# XOR_1_1.net
KiCad netlist of a schematic drawn in EAGLE
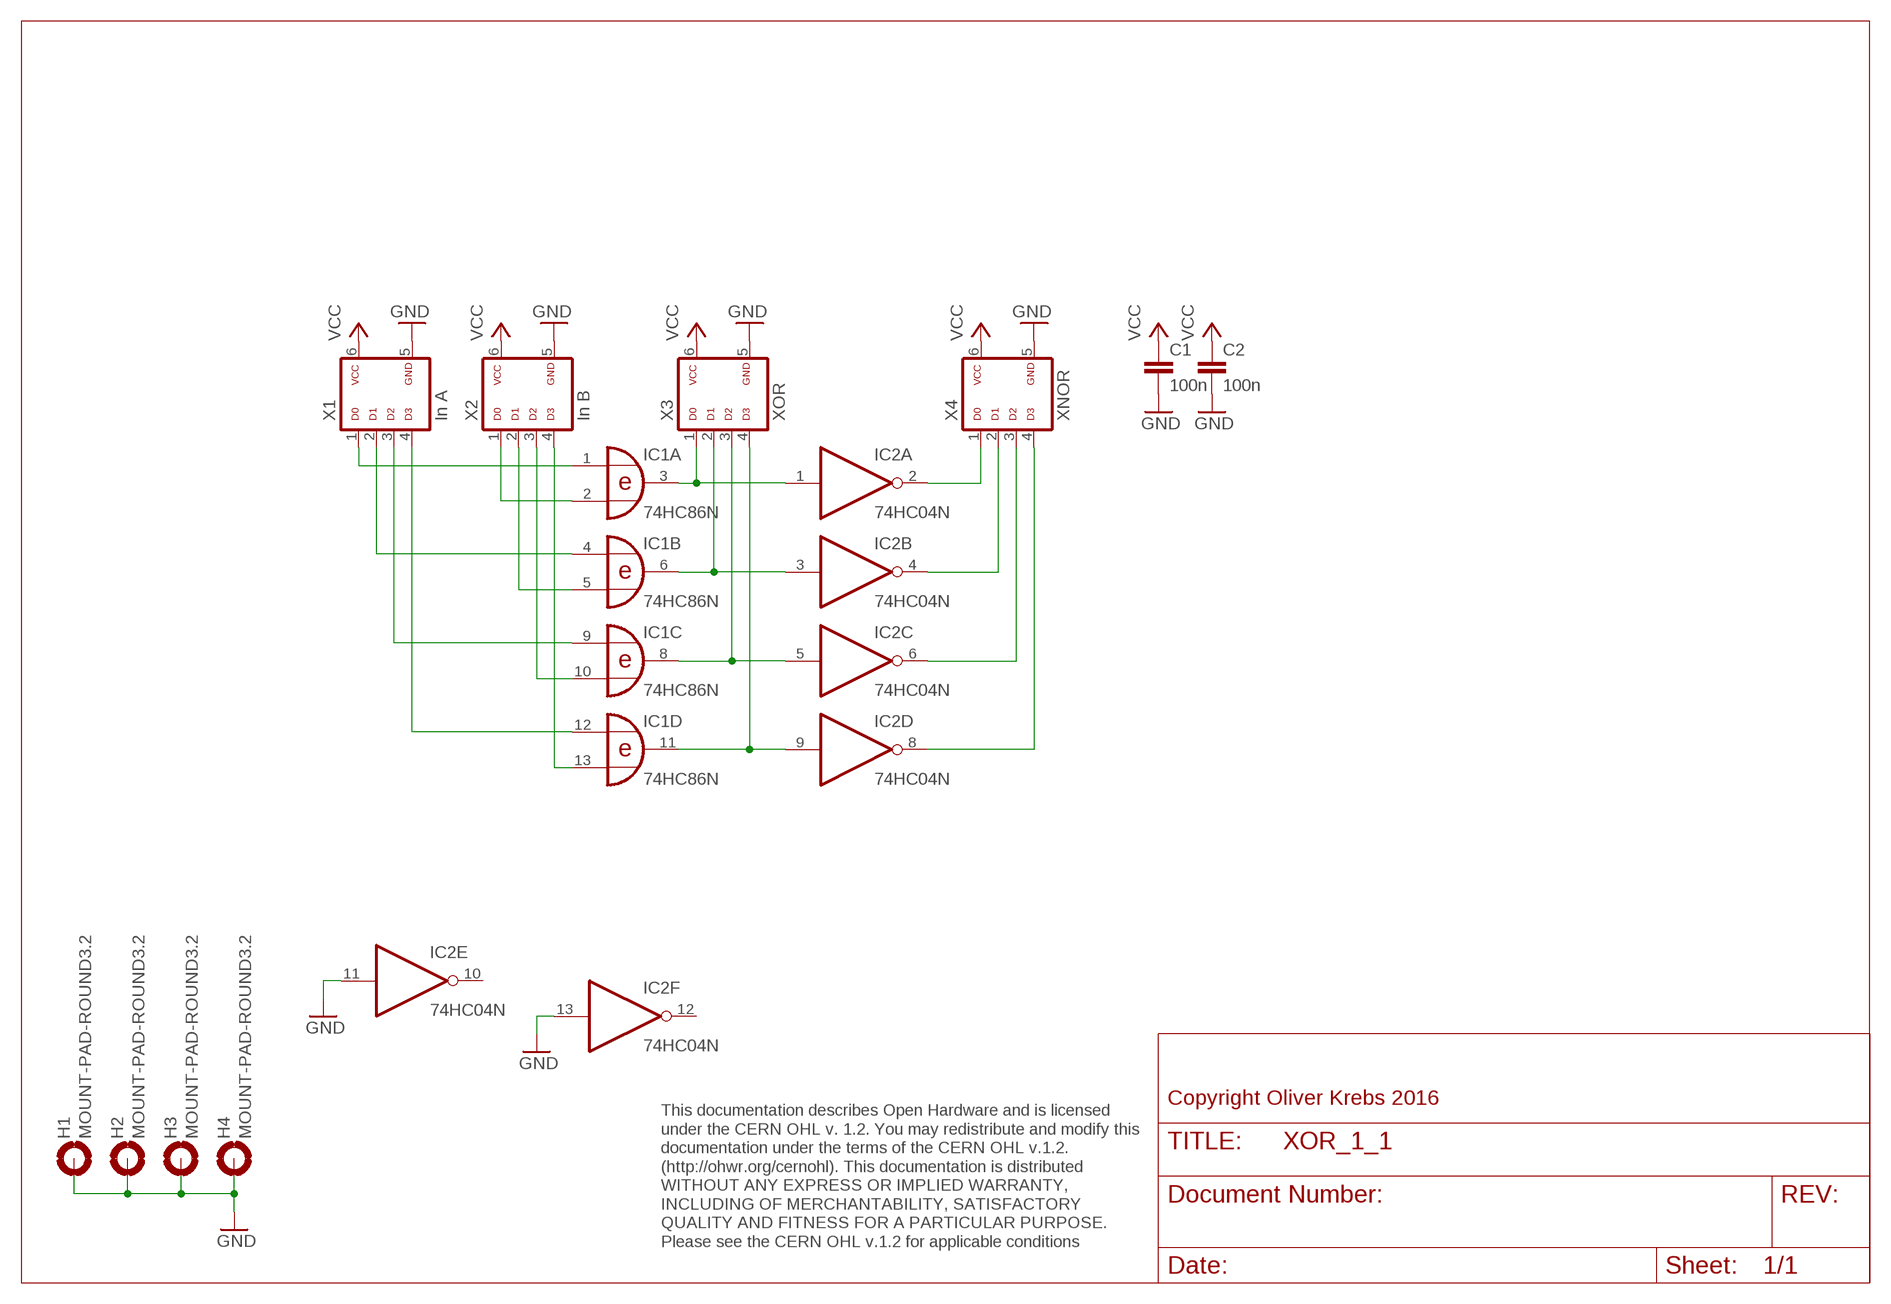
[diagram p0: schematic, sheet 1]

(export (version "E")
  (design (tool "Eeschema 10.0.6"))
  (components
    (comp (ref "C1")
      (value "100n")
      (footprint "eagle-import:C050-025X075")
      (libsource (lib "eagle-import") (part "C-EU050-025X075"))
    )
    (comp (ref "C2")
      (value "100n")
      (footprint "eagle-import:C050-025X075")
      (libsource (lib "eagle-import") (part "C-EU050-025X075"))
    )
    (comp (ref "H1")
      (value "MOUNT-PAD-ROUND3.2")
      (footprint "eagle-import:3,2-PAD")
      (libsource (lib "eagle-import") (part "MOUNT-PAD-ROUND3.2"))
    )
    (comp (ref "H2")
      (value "MOUNT-PAD-ROUND3.2")
      (footprint "eagle-import:3,2-PAD")
      (libsource (lib "eagle-import") (part "MOUNT-PAD-ROUND3.2"))
    )
    (comp (ref "H3")
      (value "MOUNT-PAD-ROUND3.2")
      (footprint "eagle-import:3,2-PAD")
      (libsource (lib "eagle-import") (part "MOUNT-PAD-ROUND3.2"))
    )
    (comp (ref "H4")
      (value "MOUNT-PAD-ROUND3.2")
      (footprint "eagle-import:3,2-PAD")
      (libsource (lib "eagle-import") (part "MOUNT-PAD-ROUND3.2"))
    )
    (comp (ref "IC1")
      (value "74HC86N")
      (footprint "eagle-import:DIL14")
      (libsource (lib "eagle-import") (part "7486NHC"))
    )
    (comp (ref "IC2")
      (value "74HC04N")
      (footprint "eagle-import:DIL14")
      (libsource (lib "eagle-import") (part "7404NHC"))
    )
    (comp (ref "X1")
      (value "In A")
      (footprint "eagle-import:ML-6")
      (libsource (lib "eagle-import") (part "ML6D"))
    )
    (comp (ref "X2")
      (value "In B")
      (footprint "eagle-import:ML-6")
      (libsource (lib "eagle-import") (part "ML6D"))
    )
    (comp (ref "X3")
      (value "XOR")
      (footprint "eagle-import:ML-6")
      (libsource (lib "eagle-import") (part "ML6D"))
    )
    (comp (ref "X4")
      (value "XNOR")
      (footprint "eagle-import:ML-6")
      (libsource (lib "eagle-import") (part "ML6D"))
    )
  )
  (nets
    (net (code "1") (name "GND") (class "Default")
      (node (ref "C1") (pin "2") (pinfunction "2_2") (pintype "passive"))
      (node (ref "C2") (pin "2") (pinfunction "2_2") (pintype "passive"))
      (node (ref "H1") (pin "B3,2") (pinfunction "MOUNT_B3,2") (pintype "passive"))
      (node (ref "H2") (pin "B3,2") (pinfunction "MOUNT_B3,2") (pintype "passive"))
      (node (ref "H3") (pin "B3,2") (pinfunction "MOUNT_B3,2") (pintype "passive"))
      (node (ref "H4") (pin "B3,2") (pinfunction "MOUNT_B3,2") (pintype "passive"))
      (node (ref "IC2") (pin "11") (pinfunction "I_11") (pintype "input"))
      (node (ref "IC2") (pin "13") (pinfunction "I_13") (pintype "input"))
      (node (ref "X1") (pin "5") (pinfunction "5_5") (pintype "passive"))
      (node (ref "X2") (pin "5") (pinfunction "5_5") (pintype "passive"))
      (node (ref "X3") (pin "5") (pinfunction "5_5") (pintype "passive"))
      (node (ref "X4") (pin "5") (pinfunction "5_5") (pintype "passive"))
    )
    (net (code "2") (name "Net-(IC1A-I0)") (class "Default")
      (node (ref "IC1") (pin "1") (pinfunction "I0_1") (pintype "input"))
      (node (ref "X1") (pin "1") (pinfunction "1_1") (pintype "passive"))
    )
    (net (code "3") (name "Net-(IC1A-I1)") (class "Default")
      (node (ref "IC1") (pin "2") (pinfunction "I1_2") (pintype "input"))
      (node (ref "X2") (pin "1") (pinfunction "1_1") (pintype "passive"))
    )
    (net (code "4") (name "Net-(IC1A-O)") (class "Default")
      (node (ref "IC1") (pin "3") (pinfunction "O_3") (pintype "output"))
      (node (ref "IC2") (pin "1") (pinfunction "I_1") (pintype "input"))
      (node (ref "X3") (pin "1") (pinfunction "1_1") (pintype "passive"))
    )
    (net (code "5") (name "Net-(IC1B-I0)") (class "Default")
      (node (ref "IC1") (pin "4") (pinfunction "I0_4") (pintype "input"))
      (node (ref "X1") (pin "2") (pinfunction "2_2") (pintype "passive"))
    )
    (net (code "6") (name "Net-(IC1B-I1)") (class "Default")
      (node (ref "IC1") (pin "5") (pinfunction "I1_5") (pintype "input"))
      (node (ref "X2") (pin "2") (pinfunction "2_2") (pintype "passive"))
    )
    (net (code "7") (name "Net-(IC1B-O)") (class "Default")
      (node (ref "IC1") (pin "6") (pinfunction "O_6") (pintype "output"))
      (node (ref "IC2") (pin "3") (pinfunction "I_3") (pintype "input"))
      (node (ref "X3") (pin "2") (pinfunction "2_2") (pintype "passive"))
    )
    (net (code "8") (name "Net-(IC1C-I0)") (class "Default")
      (node (ref "IC1") (pin "9") (pinfunction "I0_9") (pintype "input"))
      (node (ref "X1") (pin "3") (pinfunction "3_3") (pintype "passive"))
    )
    (net (code "9") (name "Net-(IC1C-I1)") (class "Default")
      (node (ref "IC1") (pin "10") (pinfunction "I1_10") (pintype "input"))
      (node (ref "X2") (pin "3") (pinfunction "3_3") (pintype "passive"))
    )
    (net (code "10") (name "Net-(IC1C-O)") (class "Default")
      (node (ref "IC1") (pin "8") (pinfunction "O_8") (pintype "output"))
      (node (ref "IC2") (pin "5") (pinfunction "I_5") (pintype "input"))
      (node (ref "X3") (pin "3") (pinfunction "3_3") (pintype "passive"))
    )
    (net (code "11") (name "Net-(IC1D-I0)") (class "Default")
      (node (ref "IC1") (pin "12") (pinfunction "I0_12") (pintype "input"))
      (node (ref "X1") (pin "4") (pinfunction "4_4") (pintype "passive"))
    )
    (net (code "12") (name "Net-(IC1D-I1)") (class "Default")
      (node (ref "IC1") (pin "13") (pinfunction "I1_13") (pintype "input"))
      (node (ref "X2") (pin "4") (pinfunction "4_4") (pintype "passive"))
    )
    (net (code "13") (name "Net-(IC1D-O)") (class "Default")
      (node (ref "IC1") (pin "11") (pinfunction "O_11") (pintype "output"))
      (node (ref "IC2") (pin "9") (pinfunction "I_9") (pintype "input"))
      (node (ref "X3") (pin "4") (pinfunction "4_4") (pintype "passive"))
    )
    (net (code "14") (name "Net-(IC2A-O)") (class "Default")
      (node (ref "IC2") (pin "2") (pinfunction "O_2") (pintype "output"))
      (node (ref "X4") (pin "1") (pinfunction "1_1") (pintype "passive"))
    )
    (net (code "15") (name "Net-(IC2B-O)") (class "Default")
      (node (ref "IC2") (pin "4") (pinfunction "O_4") (pintype "output"))
      (node (ref "X4") (pin "2") (pinfunction "2_2") (pintype "passive"))
    )
    (net (code "16") (name "Net-(IC2C-O)") (class "Default")
      (node (ref "IC2") (pin "6") (pinfunction "O_6") (pintype "output"))
      (node (ref "X4") (pin "3") (pinfunction "3_3") (pintype "passive"))
    )
    (net (code "17") (name "Net-(IC2D-O)") (class "Default")
      (node (ref "IC2") (pin "8") (pinfunction "O_8") (pintype "output"))
      (node (ref "X4") (pin "4") (pinfunction "4_4") (pintype "passive"))
    )
    (net (code "18") (name "VCC") (class "Default")
      (node (ref "C1") (pin "1") (pinfunction "1_1") (pintype "passive"))
      (node (ref "C2") (pin "1") (pinfunction "1_1") (pintype "passive"))
      (node (ref "X1") (pin "6") (pinfunction "6_6") (pintype "passive"))
      (node (ref "X2") (pin "6") (pinfunction "6_6") (pintype "passive"))
      (node (ref "X3") (pin "6") (pinfunction "6_6") (pintype "passive"))
      (node (ref "X4") (pin "6") (pinfunction "6_6") (pintype "passive"))
    )
    (net (code "19") (name "unconnected-(IC2E-O-Pad10)") (class "Default")
      (node (ref "IC2") (pin "10") (pinfunction "O_10") (pintype "output"))
    )
    (net (code "20") (name "unconnected-(IC2F-O-Pad12)") (class "Default")
      (node (ref "IC2") (pin "12") (pinfunction "O_12") (pintype "output"))
    )
  )
)
